# main.net
KiCad netlist of a schematic drawn in Altium Designer
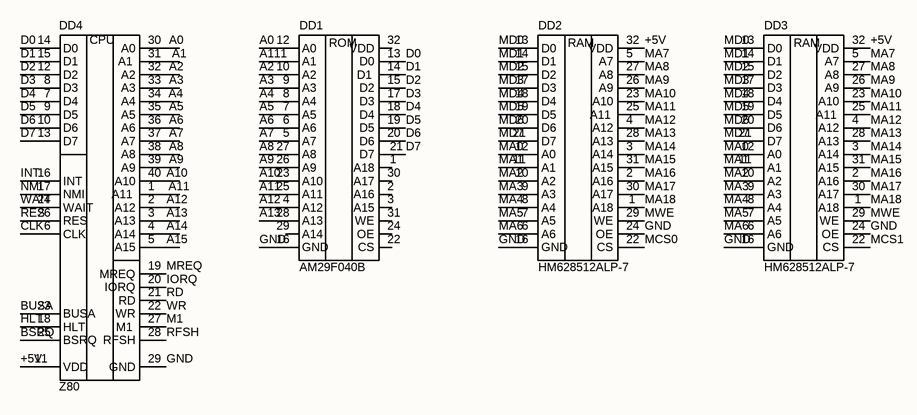
[diagram p0: main.SchDoc]

(export (version "E")
  (design (tool "Eeschema 10.0.6"))
  (components
    (comp (ref "DD1")
      (value "AM29F040B")
      (footprint "DIP254P1524X482-32")
      (libsource (lib "ROM") (part "AM29F040B"))
    )
    (comp (ref "DD2")
      (value "HM628512ALP-7")
      (footprint "DIP254P1524X482-32")
      (description "512Kx8 Static RAM")
      (libsource (lib "RAM") (part "HM628512ALP-7"))
    )
    (comp (ref "DD3")
      (value "HM628512ALP-7")
      (footprint "DIP254P1524X482-32")
      (description "512Kx8 Static RAM")
      (libsource (lib "RAM") (part "HM628512ALP-7"))
    )
    (comp (ref "DD4")
      (value "Z80")
      (footprint "DIP1540W47P254L5320H635Q40B")
      (libsource (lib "Z80") (part "Z80"))
    )
  )
  (nets
    (net (code "1") (name "/+5V") (class "Default")
      (node (ref "DD2") (pin "32") (pinfunction "VDD_32") (pintype "passive"))
      (node (ref "DD3") (pin "32") (pinfunction "VDD_32") (pintype "passive"))
      (node (ref "DD4") (pin "11") (pinfunction "VDD_11") (pintype "passive"))
    )
    (net (code "2") (name "/A0") (class "Default")
      (node (ref "DD1") (pin "12") (pinfunction "A0_12") (pintype "passive"))
      (node (ref "DD4") (pin "30") (pinfunction "A0_30") (pintype "passive"))
    )
    (net (code "3") (name "/A1") (class "Default")
      (node (ref "DD1") (pin "11") (pinfunction "A1_11") (pintype "passive"))
      (node (ref "DD4") (pin "31") (pinfunction "A1_31") (pintype "passive"))
    )
    (net (code "4") (name "/A2") (class "Default")
      (node (ref "DD1") (pin "10") (pinfunction "A2_10") (pintype "passive"))
      (node (ref "DD4") (pin "32") (pinfunction "A2_32") (pintype "passive"))
    )
    (net (code "5") (name "/A3") (class "Default")
      (node (ref "DD1") (pin "9") (pinfunction "A3_9") (pintype "passive"))
      (node (ref "DD4") (pin "33") (pinfunction "A3_33") (pintype "passive"))
    )
    (net (code "6") (name "/A4") (class "Default")
      (node (ref "DD1") (pin "8") (pinfunction "A4_8") (pintype "passive"))
      (node (ref "DD4") (pin "34") (pinfunction "A4_34") (pintype "passive"))
    )
    (net (code "7") (name "/A5") (class "Default")
      (node (ref "DD1") (pin "7") (pinfunction "A5_7") (pintype "passive"))
      (node (ref "DD4") (pin "35") (pinfunction "A5_35") (pintype "passive"))
    )
    (net (code "8") (name "/A6") (class "Default")
      (node (ref "DD1") (pin "6") (pinfunction "A6_6") (pintype "passive"))
      (node (ref "DD4") (pin "36") (pinfunction "A6_36") (pintype "passive"))
    )
    (net (code "9") (name "/A7") (class "Default")
      (node (ref "DD1") (pin "5") (pinfunction "A7_5") (pintype "passive"))
      (node (ref "DD4") (pin "37") (pinfunction "A7_37") (pintype "passive"))
    )
    (net (code "10") (name "/A8") (class "Default")
      (node (ref "DD1") (pin "27") (pinfunction "A8_27") (pintype "passive"))
      (node (ref "DD4") (pin "38") (pinfunction "A8_38") (pintype "passive"))
    )
    (net (code "11") (name "/A9") (class "Default")
      (node (ref "DD1") (pin "26") (pinfunction "A9_26") (pintype "passive"))
      (node (ref "DD4") (pin "39") (pinfunction "A9_39") (pintype "passive"))
    )
    (net (code "12") (name "/A10") (class "Default")
      (node (ref "DD1") (pin "23") (pinfunction "A10_23") (pintype "passive"))
      (node (ref "DD4") (pin "40") (pinfunction "A10_40") (pintype "passive"))
    )
    (net (code "13") (name "/A11") (class "Default")
      (node (ref "DD1") (pin "25") (pinfunction "A11_25") (pintype "passive"))
      (node (ref "DD4") (pin "1") (pinfunction "A11_1") (pintype "passive"))
    )
    (net (code "14") (name "/A12") (class "Default")
      (node (ref "DD1") (pin "4") (pinfunction "A12_4") (pintype "passive"))
      (node (ref "DD4") (pin "2") (pinfunction "A12_2") (pintype "passive"))
    )
    (net (code "15") (name "/A13") (class "Default")
      (node (ref "DD1") (pin "28") (pinfunction "A13_28") (pintype "passive"))
      (node (ref "DD4") (pin "3") (pinfunction "A13_3") (pintype "passive"))
    )
    (net (code "16") (name "/A14") (class "Default")
      (node (ref "DD4") (pin "4") (pinfunction "A14_4") (pintype "passive"))
    )
    (net (code "17") (name "/A15") (class "Default")
      (node (ref "DD4") (pin "5") (pinfunction "A15_5") (pintype "passive"))
    )
    (net (code "18") (name "/BSRQ") (class "Default")
      (node (ref "DD4") (pin "25") (pinfunction "BSRQ_25") (pintype "passive"))
    )
    (net (code "19") (name "/BUSA") (class "Default")
      (node (ref "DD4") (pin "23") (pinfunction "BUSA_23") (pintype "passive"))
    )
    (net (code "20") (name "/CLK") (class "Default")
      (node (ref "DD4") (pin "6") (pinfunction "CLK_6") (pintype "passive"))
    )
    (net (code "21") (name "/D0") (class "Default")
      (node (ref "DD1") (pin "13") (pinfunction "D0_13") (pintype "passive"))
      (node (ref "DD4") (pin "14") (pinfunction "D0_14") (pintype "passive"))
    )
    (net (code "22") (name "/D1") (class "Default")
      (node (ref "DD1") (pin "14") (pinfunction "D1_14") (pintype "passive"))
      (node (ref "DD4") (pin "15") (pinfunction "D1_15") (pintype "passive"))
    )
    (net (code "23") (name "/D2") (class "Default")
      (node (ref "DD1") (pin "15") (pinfunction "D2_15") (pintype "passive"))
      (node (ref "DD4") (pin "12") (pinfunction "D2_12") (pintype "passive"))
    )
    (net (code "24") (name "/D3") (class "Default")
      (node (ref "DD1") (pin "17") (pinfunction "D3_17") (pintype "passive"))
      (node (ref "DD4") (pin "8") (pinfunction "D3_8") (pintype "passive"))
    )
    (net (code "25") (name "/D4") (class "Default")
      (node (ref "DD1") (pin "18") (pinfunction "D4_18") (pintype "passive"))
      (node (ref "DD4") (pin "7") (pinfunction "D4_7") (pintype "passive"))
    )
    (net (code "26") (name "/D5") (class "Default")
      (node (ref "DD1") (pin "19") (pinfunction "D5_19") (pintype "passive"))
      (node (ref "DD4") (pin "9") (pinfunction "D5_9") (pintype "passive"))
    )
    (net (code "27") (name "/D6") (class "Default")
      (node (ref "DD1") (pin "20") (pinfunction "D6_20") (pintype "passive"))
      (node (ref "DD4") (pin "10") (pinfunction "D6_10") (pintype "passive"))
    )
    (net (code "28") (name "/D7") (class "Default")
      (node (ref "DD1") (pin "21") (pinfunction "D7_21") (pintype "passive"))
      (node (ref "DD4") (pin "13") (pinfunction "D7_13") (pintype "passive"))
    )
    (net (code "29") (name "/GND") (class "Default")
      (node (ref "DD1") (pin "16") (pinfunction "GND_16") (pintype "passive"))
      (node (ref "DD2") (pin "16") (pinfunction "GND_16") (pintype "passive"))
      (node (ref "DD2") (pin "24") (pinfunction "OE_24") (pintype "passive"))
      (node (ref "DD3") (pin "16") (pinfunction "GND_16") (pintype "passive"))
      (node (ref "DD3") (pin "24") (pinfunction "OE_24") (pintype "passive"))
      (node (ref "DD4") (pin "29") (pinfunction "GND_29") (pintype "passive"))
    )
    (net (code "30") (name "/HLT") (class "Default")
      (node (ref "DD4") (pin "18") (pinfunction "HLT_18") (pintype "passive"))
    )
    (net (code "31") (name "/INT") (class "Default")
      (node (ref "DD4") (pin "16") (pinfunction "INT_16") (pintype "passive"))
    )
    (net (code "32") (name "/IORQ") (class "Default")
      (node (ref "DD4") (pin "20") (pinfunction "IORQ_20") (pintype "passive"))
    )
    (net (code "33") (name "/M1") (class "Default")
      (node (ref "DD4") (pin "27") (pinfunction "M1_27") (pintype "passive"))
    )
    (net (code "34") (name "/MA0") (class "Default")
      (node (ref "DD2") (pin "12") (pinfunction "A0_12") (pintype "passive"))
      (node (ref "DD3") (pin "12") (pinfunction "A0_12") (pintype "passive"))
    )
    (net (code "35") (name "/MA1") (class "Default")
      (node (ref "DD2") (pin "11") (pinfunction "A1_11") (pintype "passive"))
      (node (ref "DD3") (pin "11") (pinfunction "A1_11") (pintype "passive"))
    )
    (net (code "36") (name "/MA2") (class "Default")
      (node (ref "DD2") (pin "10") (pinfunction "A2_10") (pintype "passive"))
      (node (ref "DD3") (pin "10") (pinfunction "A2_10") (pintype "passive"))
    )
    (net (code "37") (name "/MA3") (class "Default")
      (node (ref "DD2") (pin "9") (pinfunction "A3_9") (pintype "passive"))
      (node (ref "DD3") (pin "9") (pinfunction "A3_9") (pintype "passive"))
    )
    (net (code "38") (name "/MA4") (class "Default")
      (node (ref "DD2") (pin "8") (pinfunction "A4_8") (pintype "passive"))
      (node (ref "DD3") (pin "8") (pinfunction "A4_8") (pintype "passive"))
    )
    (net (code "39") (name "/MA5") (class "Default")
      (node (ref "DD2") (pin "7") (pinfunction "A5_7") (pintype "passive"))
      (node (ref "DD3") (pin "7") (pinfunction "A5_7") (pintype "passive"))
    )
    (net (code "40") (name "/MA6") (class "Default")
      (node (ref "DD2") (pin "6") (pinfunction "A6_6") (pintype "passive"))
      (node (ref "DD3") (pin "6") (pinfunction "A6_6") (pintype "passive"))
    )
    (net (code "41") (name "/MA7") (class "Default")
      (node (ref "DD2") (pin "5") (pinfunction "A7_5") (pintype "passive"))
      (node (ref "DD3") (pin "5") (pinfunction "A7_5") (pintype "passive"))
    )
    (net (code "42") (name "/MA8") (class "Default")
      (node (ref "DD2") (pin "27") (pinfunction "A8_27") (pintype "passive"))
      (node (ref "DD3") (pin "27") (pinfunction "A8_27") (pintype "passive"))
    )
    (net (code "43") (name "/MA9") (class "Default")
      (node (ref "DD2") (pin "26") (pinfunction "A9_26") (pintype "passive"))
      (node (ref "DD3") (pin "26") (pinfunction "A9_26") (pintype "passive"))
    )
    (net (code "44") (name "/MA10") (class "Default")
      (node (ref "DD2") (pin "23") (pinfunction "A10_23") (pintype "passive"))
      (node (ref "DD3") (pin "23") (pinfunction "A10_23") (pintype "passive"))
    )
    (net (code "45") (name "/MA11") (class "Default")
      (node (ref "DD2") (pin "25") (pinfunction "A11_25") (pintype "passive"))
      (node (ref "DD3") (pin "25") (pinfunction "A11_25") (pintype "passive"))
    )
    (net (code "46") (name "/MA12") (class "Default")
      (node (ref "DD2") (pin "4") (pinfunction "A12_4") (pintype "passive"))
      (node (ref "DD3") (pin "4") (pinfunction "A12_4") (pintype "passive"))
    )
    (net (code "47") (name "/MA13") (class "Default")
      (node (ref "DD2") (pin "28") (pinfunction "A13_28") (pintype "passive"))
      (node (ref "DD3") (pin "28") (pinfunction "A13_28") (pintype "passive"))
    )
    (net (code "48") (name "/MA14") (class "Default")
      (node (ref "DD2") (pin "3") (pinfunction "A14_3") (pintype "passive"))
      (node (ref "DD3") (pin "3") (pinfunction "A14_3") (pintype "passive"))
    )
    (net (code "49") (name "/MA15") (class "Default")
      (node (ref "DD2") (pin "31") (pinfunction "A15_31") (pintype "passive"))
      (node (ref "DD3") (pin "31") (pinfunction "A15_31") (pintype "passive"))
    )
    (net (code "50") (name "/MA16") (class "Default")
      (node (ref "DD2") (pin "2") (pinfunction "A16_2") (pintype "passive"))
      (node (ref "DD3") (pin "2") (pinfunction "A16_2") (pintype "passive"))
    )
    (net (code "51") (name "/MA17") (class "Default")
      (node (ref "DD2") (pin "30") (pinfunction "A17_30") (pintype "passive"))
      (node (ref "DD3") (pin "30") (pinfunction "A17_30") (pintype "passive"))
    )
    (net (code "52") (name "/MA18") (class "Default")
      (node (ref "DD2") (pin "1") (pinfunction "A18_1") (pintype "passive"))
      (node (ref "DD3") (pin "1") (pinfunction "A18_1") (pintype "passive"))
    )
    (net (code "53") (name "/MCS0") (class "Default")
      (node (ref "DD2") (pin "22") (pinfunction "CS_22") (pintype "passive"))
    )
    (net (code "54") (name "/MCS1") (class "Default")
      (node (ref "DD3") (pin "22") (pinfunction "CS_22") (pintype "passive"))
    )
    (net (code "55") (name "/MD0") (class "Default")
      (node (ref "DD2") (pin "13") (pinfunction "D0_13") (pintype "passive"))
      (node (ref "DD3") (pin "13") (pinfunction "D0_13") (pintype "passive"))
    )
    (net (code "56") (name "/MD1") (class "Default")
      (node (ref "DD2") (pin "14") (pinfunction "D1_14") (pintype "passive"))
      (node (ref "DD3") (pin "14") (pinfunction "D1_14") (pintype "passive"))
    )
    (net (code "57") (name "/MD2") (class "Default")
      (node (ref "DD2") (pin "15") (pinfunction "D2_15") (pintype "passive"))
      (node (ref "DD3") (pin "15") (pinfunction "D2_15") (pintype "passive"))
    )
    (net (code "58") (name "/MD3") (class "Default")
      (node (ref "DD2") (pin "17") (pinfunction "D3_17") (pintype "passive"))
      (node (ref "DD3") (pin "17") (pinfunction "D3_17") (pintype "passive"))
    )
    (net (code "59") (name "/MD4") (class "Default")
      (node (ref "DD2") (pin "18") (pinfunction "D4_18") (pintype "passive"))
      (node (ref "DD3") (pin "18") (pinfunction "D4_18") (pintype "passive"))
    )
    (net (code "60") (name "/MD5") (class "Default")
      (node (ref "DD2") (pin "19") (pinfunction "D5_19") (pintype "passive"))
      (node (ref "DD3") (pin "19") (pinfunction "D5_19") (pintype "passive"))
    )
    (net (code "61") (name "/MD6") (class "Default")
      (node (ref "DD2") (pin "20") (pinfunction "D6_20") (pintype "passive"))
      (node (ref "DD3") (pin "20") (pinfunction "D6_20") (pintype "passive"))
    )
    (net (code "62") (name "/MD7") (class "Default")
      (node (ref "DD2") (pin "21") (pinfunction "D7_21") (pintype "passive"))
      (node (ref "DD3") (pin "21") (pinfunction "D7_21") (pintype "passive"))
    )
    (net (code "63") (name "/MREQ") (class "Default")
      (node (ref "DD4") (pin "19") (pinfunction "MREQ_19") (pintype "passive"))
    )
    (net (code "64") (name "/MWE") (class "Default")
      (node (ref "DD2") (pin "29") (pinfunction "WE_29") (pintype "passive"))
      (node (ref "DD3") (pin "29") (pinfunction "WE_29") (pintype "passive"))
    )
    (net (code "65") (name "/NMI") (class "Default")
      (node (ref "DD4") (pin "17") (pinfunction "NMI_17") (pintype "passive"))
    )
    (net (code "66") (name "/RD") (class "Default")
      (node (ref "DD4") (pin "21") (pinfunction "RD_21") (pintype "passive"))
    )
    (net (code "67") (name "/RES") (class "Default")
      (node (ref "DD4") (pin "26") (pinfunction "RES_26") (pintype "passive"))
    )
    (net (code "68") (name "/RFSH") (class "Default")
      (node (ref "DD4") (pin "28") (pinfunction "RFSH_28") (pintype "passive"))
    )
    (net (code "69") (name "/WAIT") (class "Default")
      (node (ref "DD4") (pin "24") (pinfunction "WAIT_24") (pintype "passive"))
    )
    (net (code "70") (name "/WR") (class "Default")
      (node (ref "DD4") (pin "22") (pinfunction "WR_22") (pintype "passive"))
    )
    (net (code "71") (name "unconnected-(DD1-A14-Pad29)") (class "Default")
      (node (ref "DD1") (pin "29") (pinfunction "A14_29") (pintype "passive"))
    )
    (net (code "72") (name "unconnected-(DD1-A15-Pad3)") (class "Default")
      (node (ref "DD1") (pin "3") (pinfunction "A15_3") (pintype "passive"))
    )
    (net (code "73") (name "unconnected-(DD1-A16-Pad2)") (class "Default")
      (node (ref "DD1") (pin "2") (pinfunction "A16_2") (pintype "passive"))
    )
    (net (code "74") (name "unconnected-(DD1-A17-Pad30)") (class "Default")
      (node (ref "DD1") (pin "30") (pinfunction "A17_30") (pintype "passive"))
    )
    (net (code "75") (name "unconnected-(DD1-A18-Pad1)") (class "Default")
      (node (ref "DD1") (pin "1") (pinfunction "A18_1") (pintype "passive"))
    )
    (net (code "76") (name "unconnected-(DD1-CS-Pad22)") (class "Default")
      (node (ref "DD1") (pin "22") (pinfunction "CS_22") (pintype "passive"))
    )
    (net (code "77") (name "unconnected-(DD1-OE-Pad24)") (class "Default")
      (node (ref "DD1") (pin "24") (pinfunction "OE_24") (pintype "passive"))
    )
    (net (code "78") (name "unconnected-(DD1-VDD-Pad32)") (class "Default")
      (node (ref "DD1") (pin "32") (pinfunction "VDD_32") (pintype "passive"))
    )
    (net (code "79") (name "unconnected-(DD1-WE-Pad31)") (class "Default")
      (node (ref "DD1") (pin "31") (pinfunction "WE_31") (pintype "passive"))
    )
  )
)
